# orblink.net
KiCad netlist of a schematic drawn in EAGLE
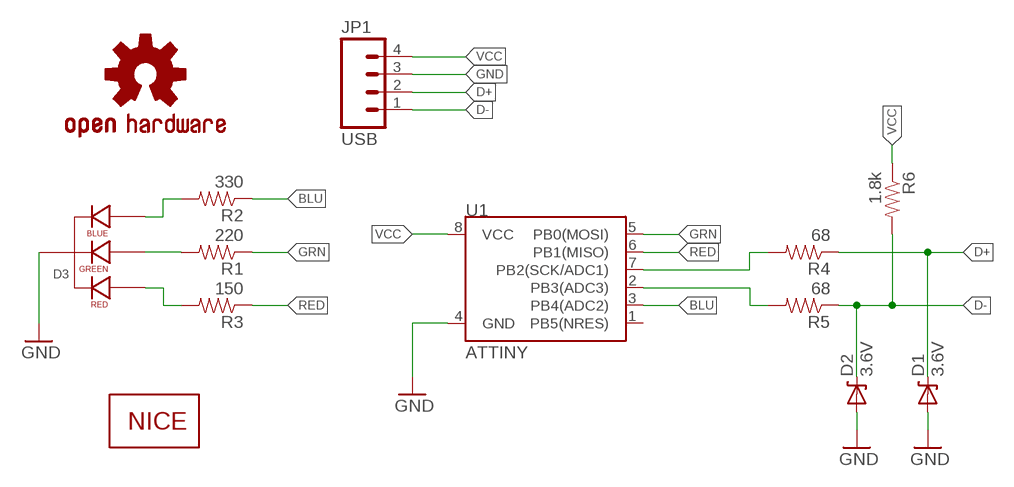
[diagram p0: schematic, sheet 1]

(export (version "E")
  (design (tool "Eeschema 10.0.6"))
  (components
    (comp (ref "D1")
      (value "3.6V")
      (footprint "eagle-import:DIODE-ZENER")
      (libsource (lib "eagle-import") (part "DIODE-ZENERPTH"))
    )
    (comp (ref "D2")
      (value "3.6V")
      (footprint "eagle-import:DIODE-ZENER")
      (libsource (lib "eagle-import") (part "DIODE-ZENERPTH"))
    )
    (comp (ref "D3")
      (value "LED-RGB-CC-THRUDIFFUSE")
      (footprint "eagle-import:LED-RGB-THRU")
      (libsource (lib "eagle-import") (part "LED-RGB-CC-THRUDIFFUSE"))
    )
    (comp (ref "JP1")
      (value "USB")
      (footprint "eagle-import:1X04")
      (libsource (lib "eagle-import") (part "M04PTH"))
    )
    (comp (ref "LOGO1")
      (value "OSHW-LOGOS")
      (footprint "eagle-import:OSHW-LOGO-S")
      (libsource (lib "eagle-import") (part "OSHW-LOGOS"))
    )
    (comp (ref "R1")
      (value "220")
      (footprint "eagle-import:1_6W-RES")
      (libsource (lib "eagle-import") (part "RESISTORPTH-1/6W"))
    )
    (comp (ref "R2")
      (value "330")
      (footprint "eagle-import:1_6W-RES")
      (libsource (lib "eagle-import") (part "RESISTORPTH-1/6W"))
    )
    (comp (ref "R3")
      (value "150")
      (footprint "eagle-import:1_6W-RES")
      (libsource (lib "eagle-import") (part "RESISTORPTH-1/6W"))
    )
    (comp (ref "R4")
      (value "68")
      (footprint "eagle-import:1_6W-RES")
      (libsource (lib "eagle-import") (part "RESISTORPTH-1/6W"))
    )
    (comp (ref "R5")
      (value "68")
      (footprint "eagle-import:1_6W-RES")
      (libsource (lib "eagle-import") (part "RESISTORPTH-1/6W"))
    )
    (comp (ref "R6")
      (value "1.8k")
      (footprint "eagle-import:1_6W-RES")
      (libsource (lib "eagle-import") (part "RESISTORPTH-1/6W"))
    )
    (comp (ref "U$1")
      (value "NICE-LOGO04")
      (footprint "eagle-import:NICE-LOGO-04")
      (libsource (lib "eagle-import") (part "NICE-LOGO04"))
    )
    (comp (ref "U1")
      (value "ATTINY")
      (footprint "eagle-import:DIP08")
      (libsource (lib "eagle-import") (part "ATTINY45TINY85-20-DIP"))
    )
  )
  (nets
    (net (code "1") (name "BLU") (class "Default")
      (node (ref "R2") (pin "1") (pinfunction "1_1") (pintype "passive"))
      (node (ref "U1") (pin "3") (pinfunction "PB4(ADC2)_3") (pintype "bidirectional"))
    )
    (net (code "2") (name "D+") (class "Default")
      (node (ref "D1") (pin "P$1") (pinfunction "C_P$1") (pintype "passive"))
      (node (ref "JP1") (pin "2") (pinfunction "2_2") (pintype "passive"))
      (node (ref "R4") (pin "1") (pinfunction "1_1") (pintype "passive"))
    )
    (net (code "3") (name "D-") (class "Default")
      (node (ref "D2") (pin "P$1") (pinfunction "C_P$1") (pintype "passive"))
      (node (ref "JP1") (pin "1") (pinfunction "1_1") (pintype "passive"))
      (node (ref "R5") (pin "1") (pinfunction "1_1") (pintype "passive"))
      (node (ref "R6") (pin "2") (pinfunction "2_2") (pintype "passive"))
    )
    (net (code "4") (name "GND") (class "Default")
      (node (ref "D1") (pin "P$2") (pinfunction "A_P$2") (pintype "passive"))
      (node (ref "D2") (pin "P$2") (pinfunction "A_P$2") (pintype "passive"))
      (node (ref "D3") (pin "2") (pinfunction "CATHODE_2") (pintype "bidirectional"))
      (node (ref "JP1") (pin "3") (pinfunction "3_3") (pintype "passive"))
      (node (ref "U1") (pin "4") (pinfunction "GND_4") (pintype "bidirectional"))
    )
    (net (code "5") (name "GRN") (class "Default")
      (node (ref "R1") (pin "1") (pinfunction "1_1") (pintype "passive"))
      (node (ref "U1") (pin "5") (pinfunction "PB0(MOSI)_5") (pintype "bidirectional"))
    )
    (net (code "6") (name "Net-(D3-BLUE_CATHODE)") (class "Default")
      (node (ref "D3") (pin "4") (pinfunction "BLUE_CATHODE_4") (pintype "bidirectional"))
      (node (ref "R2") (pin "2") (pinfunction "2_2") (pintype "passive"))
    )
    (net (code "7") (name "Net-(D3-GREEN_CATHODE)") (class "Default")
      (node (ref "D3") (pin "3") (pinfunction "GREEN_CATHODE_3") (pintype "bidirectional"))
      (node (ref "R1") (pin "2") (pinfunction "2_2") (pintype "passive"))
    )
    (net (code "8") (name "Net-(D3-RED_CATHODE)") (class "Default")
      (node (ref "D3") (pin "1") (pinfunction "RED_CATHODE_1") (pintype "bidirectional"))
      (node (ref "R3") (pin "2") (pinfunction "2_2") (pintype "passive"))
    )
    (net (code "9") (name "Net-(U1-PB2(SCK{slash}ADC1))") (class "Default")
      (node (ref "R4") (pin "2") (pinfunction "2_2") (pintype "passive"))
      (node (ref "U1") (pin "7") (pinfunction "PB2(SCK/ADC1)_7") (pintype "bidirectional"))
    )
    (net (code "10") (name "Net-(U1-PB3(ADC3))") (class "Default")
      (node (ref "R5") (pin "2") (pinfunction "2_2") (pintype "passive"))
      (node (ref "U1") (pin "2") (pinfunction "PB3(ADC3)_2") (pintype "bidirectional"))
    )
    (net (code "11") (name "RED") (class "Default")
      (node (ref "R3") (pin "1") (pinfunction "1_1") (pintype "passive"))
      (node (ref "U1") (pin "6") (pinfunction "PB1(MISO)_6") (pintype "bidirectional"))
    )
    (net (code "12") (name "VCC") (class "Default")
      (node (ref "JP1") (pin "4") (pinfunction "4_4") (pintype "passive"))
      (node (ref "R6") (pin "1") (pinfunction "1_1") (pintype "passive"))
      (node (ref "U1") (pin "8") (pinfunction "VCC_8") (pintype "bidirectional"))
    )
    (net (code "13") (name "unconnected-(U1-PB5(NRES)-Pad1)") (class "Default")
      (node (ref "U1") (pin "1") (pinfunction "PB5(NRES)_1") (pintype "bidirectional"))
    )
  )
)
